# RefOsc10MHz_1V2.net
KiCad netlist of a schematic drawn in EAGLE
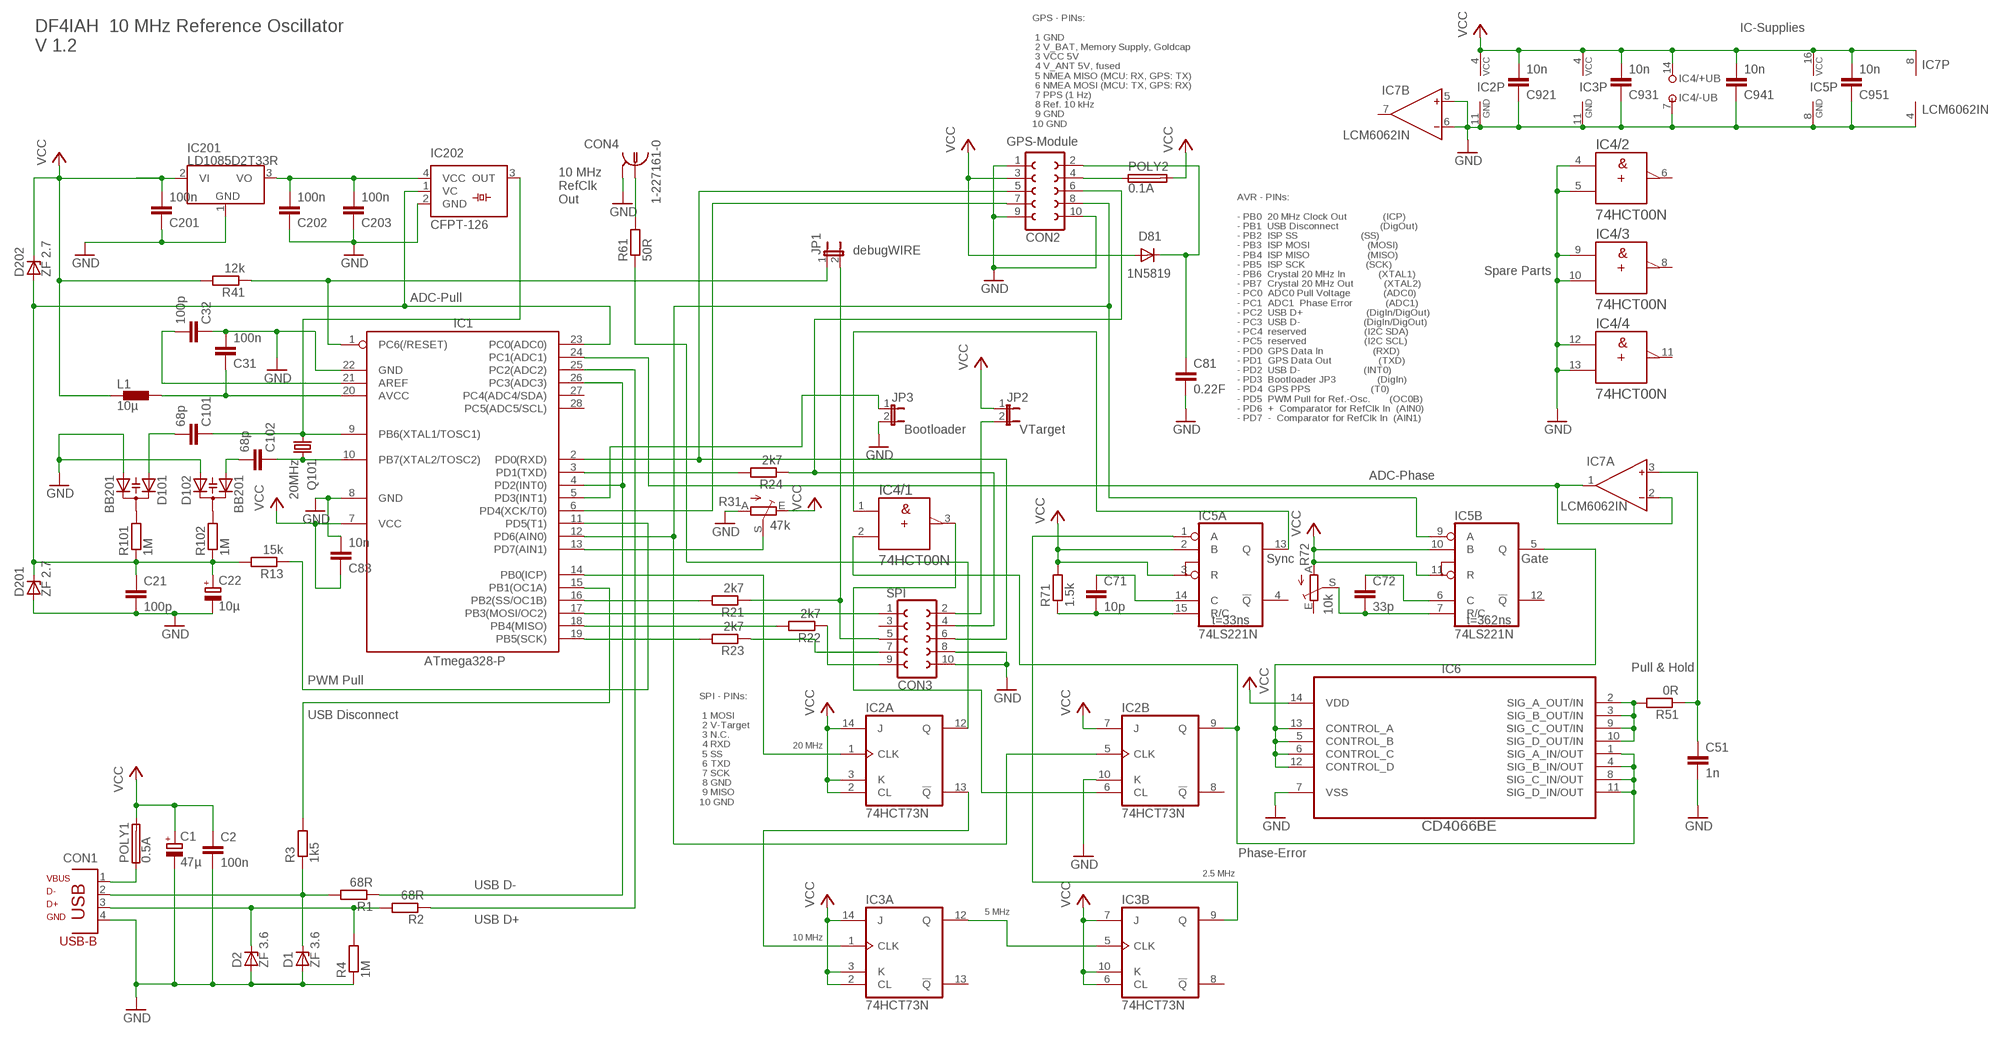
[diagram p0: schematic, sheet 1]

(export (version "E")
  (design (tool "Eeschema 10.0.6"))
  (components
    (comp (ref "C1")
      (value "47µ")
      (footprint "eagle-import:E2-4")
      (libsource (lib "eagle-import") (part "CPOL-EUE2-4"))
    )
    (comp (ref "C2")
      (value "100n")
      (footprint "eagle-import:C5B3")
      (libsource (lib "eagle-import") (part "C5/3"))
    )
    (comp (ref "C21")
      (value "100p")
      (footprint "eagle-import:C5B3")
      (libsource (lib "eagle-import") (part "C5/3"))
    )
    (comp (ref "C22")
      (value "10µ")
      (footprint "eagle-import:E2-4")
      (libsource (lib "eagle-import") (part "CPOL-EUE2-4"))
    )
    (comp (ref "C31")
      (value "100n")
      (footprint "eagle-import:C5B3")
      (libsource (lib "eagle-import") (part "C5/3"))
    )
    (comp (ref "C32")
      (value "100p")
      (footprint "eagle-import:C5B3")
      (libsource (lib "eagle-import") (part "C5/3"))
    )
    (comp (ref "C51")
      (value "1n")
      (footprint "eagle-import:C5B3")
      (libsource (lib "eagle-import") (part "C5/3"))
    )
    (comp (ref "C71")
      (value "10p")
      (footprint "eagle-import:C5B3")
      (libsource (lib "eagle-import") (part "C5/3"))
    )
    (comp (ref "C72")
      (value "33p")
      (footprint "eagle-import:C5B3")
      (libsource (lib "eagle-import") (part "C5/3"))
    )
    (comp (ref "C81")
      (value "0.22F")
      (footprint "eagle-import:C5B7.2")
      (libsource (lib "eagle-import") (part "C5/7.2"))
    )
    (comp (ref "C83")
      (value "10n")
      (footprint "eagle-import:C5B3")
      (libsource (lib "eagle-import") (part "C5/3"))
    )
    (comp (ref "C101")
      (value "68p")
      (footprint "eagle-import:C5B3")
      (libsource (lib "eagle-import") (part "C5/3"))
    )
    (comp (ref "C102")
      (value "68p")
      (footprint "eagle-import:C5B3")
      (libsource (lib "eagle-import") (part "C5/3"))
    )
    (comp (ref "C201")
      (value "100n")
      (footprint "eagle-import:C5B3")
      (libsource (lib "eagle-import") (part "C5/3"))
    )
    (comp (ref "C202")
      (value "100n")
      (footprint "eagle-import:C5B3")
      (libsource (lib "eagle-import") (part "C5/3"))
    )
    (comp (ref "C203")
      (value "100n")
      (footprint "eagle-import:C5B3")
      (libsource (lib "eagle-import") (part "C5/3"))
    )
    (comp (ref "C921")
      (value "10n")
      (footprint "eagle-import:C5B3")
      (libsource (lib "eagle-import") (part "C5/3"))
    )
    (comp (ref "C931")
      (value "10n")
      (footprint "eagle-import:C5B3")
      (libsource (lib "eagle-import") (part "C5/3"))
    )
    (comp (ref "C941")
      (value "10n")
      (footprint "eagle-import:C5B3")
      (libsource (lib "eagle-import") (part "C5/3"))
    )
    (comp (ref "C951")
      (value "10n")
      (footprint "eagle-import:C5B3")
      (libsource (lib "eagle-import") (part "C5/3"))
    )
    (comp (ref "CON1")
      (value "PN61729")
      (footprint "eagle-import:PN61729")
      (libsource (lib "eagle-import") (part "PN61729"))
    )
    (comp (ref "CON2")
      (value "FE05-2")
      (footprint "eagle-import:FE05-2")
      (libsource (lib "eagle-import") (part "FE05-2"))
    )
    (comp (ref "CON3")
      (value "FE05-2")
      (footprint "eagle-import:FE05-2")
      (libsource (lib "eagle-import") (part "FE05-2"))
    )
    (comp (ref "CON4")
      (value "1-227161-0")
      (footprint "eagle-import:AMP_227161")
      (fields (field (name "MF") "TYCO ELECTRONICS") (field (name "MPN") "1-227161"))
      (libsource (lib "eagle-import") (part "?2271611--0"))
    )
    (comp (ref "D1")
      (value "ZF 3.6")
      (footprint "eagle-import:DO41Z10")
      (libsource (lib "eagle-import") (part "1N4728"))
    )
    (comp (ref "D2")
      (value "ZF 3.6")
      (footprint "eagle-import:DO41Z10")
      (libsource (lib "eagle-import") (part "1N4728"))
    )
    (comp (ref "D81")
      (value "1N5819")
      (footprint "eagle-import:DO41-10")
      (libsource (lib "eagle-import") (part "1N4942"))
    )
    (comp (ref "D101")
      (value "BB201")
      (footprint "eagle-import:SOT23")
      (libsource (lib "eagle-import") (part "BBY51"))
    )
    (comp (ref "D102")
      (value "BB201")
      (footprint "eagle-import:SOT23")
      (libsource (lib "eagle-import") (part "BBY51"))
    )
    (comp (ref "D201")
      (value "ZF 2.7")
      (footprint "eagle-import:DO41Z10")
      (libsource (lib "eagle-import") (part "1N4728"))
    )
    (comp (ref "D202")
      (value "ZF 2.7")
      (footprint "eagle-import:DO41Z10")
      (libsource (lib "eagle-import") (part "1N4728"))
    )
    (comp (ref "IC1")
      (value "ATmega328-P")
      (footprint "eagle-import:DIL28-3")
      (libsource (lib "eagle-import") (part "MEGA8-P"))
    )
    (comp (ref "IC2")
      (value "74HCT73N")
      (footprint "eagle-import:DIL14")
      (libsource (lib "eagle-import") (part "7473NLS"))
    )
    (comp (ref "IC3")
      (value "74HCT73N")
      (footprint "eagle-import:DIL14")
      (libsource (lib "eagle-import") (part "7473NLS"))
    )
    (comp (ref "IC4")
      (value "74HCT00N")
      (footprint "eagle-import:DIL14")
      (libsource (lib "eagle-import") (part "7400NHCT"))
    )
    (comp (ref "IC5")
      (value "74LS221N")
      (footprint "eagle-import:DIL16")
      (libsource (lib "eagle-import") (part "74221NLS"))
    )
    (comp (ref "IC6")
      (value "CD4066BE")
      (footprint "eagle-import:DIP254P762X508-14")
      (libsource (lib "eagle-import") (part "CD4066BE"))
    )
    (comp (ref "IC7")
      (value "LCM6062IN")
      (footprint "eagle-import:DIL08")
      (libsource (lib "eagle-import") (part "AD822IN"))
    )
    (comp (ref "IC201")
      (value "LD10853.3")
      (footprint "eagle-import:TO220V")
      (libsource (lib "eagle-import") (part "LD10853.3"))
    )
    (comp (ref "IC202")
      (value "CFPT-126")
      (footprint "eagle-import:SM77H")
      (libsource (lib "eagle-import") (part "CFPT-126"))
    )
    (comp (ref "JP1")
      (value "JP1E")
      (footprint "eagle-import:JP1")
      (libsource (lib "eagle-import") (part "JP1E"))
    )
    (comp (ref "JP2")
      (value "JP1E")
      (footprint "eagle-import:JP1")
      (libsource (lib "eagle-import") (part "JP1E"))
    )
    (comp (ref "JP3")
      (value "JP1E")
      (footprint "eagle-import:JP1")
      (libsource (lib "eagle-import") (part "JP1E"))
    )
    (comp (ref "L1")
      (value "10µ")
      (footprint "eagle-import:BL01RN1A")
      (libsource (lib "eagle-import") (part "BL01RN1A"))
    )
    (comp (ref "POLY1")
      (value "0.5A")
      (footprint "eagle-import:TE5")
      (libsource (lib "eagle-import") (part "FUSETE5"))
    )
    (comp (ref "POLY2")
      (value "0.1A")
      (footprint "eagle-import:TE5")
      (libsource (lib "eagle-import") (part "FUSETE5"))
    )
    (comp (ref "Q101")
      (value "20MHz")
      (footprint "eagle-import:HC49U70")
      (libsource (lib "eagle-import") (part "CRYSTALHC49U70"))
    )
    (comp (ref "R1")
      (value "68R")
      (footprint "eagle-import:0204_7")
      (libsource (lib "eagle-import") (part "R-EU_0204/7"))
    )
    (comp (ref "R2")
      (value "68R")
      (footprint "eagle-import:0204_7")
      (libsource (lib "eagle-import") (part "R-EU_0204/7"))
    )
    (comp (ref "R3")
      (value "1k5")
      (footprint "eagle-import:0204_7")
      (libsource (lib "eagle-import") (part "R-EU_0204/7"))
    )
    (comp (ref "R4")
      (value "1M")
      (footprint "eagle-import:0204_7")
      (libsource (lib "eagle-import") (part "R-EU_0204/7"))
    )
    (comp (ref "R13")
      (value "15k")
      (footprint "eagle-import:0204_7")
      (libsource (lib "eagle-import") (part "R-EU_0204/7"))
    )
    (comp (ref "R21")
      (value "2k7")
      (footprint "eagle-import:0204_7")
      (libsource (lib "eagle-import") (part "R-EU_0204/7"))
    )
    (comp (ref "R22")
      (value "2k7")
      (footprint "eagle-import:0204_7")
      (libsource (lib "eagle-import") (part "R-EU_0204/7"))
    )
    (comp (ref "R23")
      (value "2k7")
      (footprint "eagle-import:0204_7")
      (libsource (lib "eagle-import") (part "R-EU_0204/7"))
    )
    (comp (ref "R24")
      (value "2k7")
      (footprint "eagle-import:0204_7")
      (libsource (lib "eagle-import") (part "R-EU_0204/7"))
    )
    (comp (ref "R31")
      (value "47k")
      (footprint "eagle-import:S64YW")
      (libsource (lib "eagle-import") (part "TRIM_1234-S64YW"))
    )
    (comp (ref "R41")
      (value "12k")
      (footprint "eagle-import:0204_7")
      (libsource (lib "eagle-import") (part "R-EU_0204/7"))
    )
    (comp (ref "R51")
      (value "0R")
      (footprint "eagle-import:0204_7")
      (libsource (lib "eagle-import") (part "R-EU_0204/7"))
    )
    (comp (ref "R61")
      (value "50R")
      (footprint "eagle-import:0204_7")
      (libsource (lib "eagle-import") (part "R-EU_0204/7"))
    )
    (comp (ref "R71")
      (value "1.5k")
      (footprint "eagle-import:0204_7")
      (libsource (lib "eagle-import") (part "R-EU_0204/7"))
    )
    (comp (ref "R72")
      (value "10k")
      (footprint "eagle-import:S64YW")
      (libsource (lib "eagle-import") (part "TRIM_1234-S64YW"))
    )
    (comp (ref "R101")
      (value "1M")
      (footprint "eagle-import:0204_7")
      (libsource (lib "eagle-import") (part "R-EU_0204/7"))
    )
    (comp (ref "R102")
      (value "1M")
      (footprint "eagle-import:0204_7")
      (libsource (lib "eagle-import") (part "R-EU_0204/7"))
    )
  )
  (nets
    (net (code "1") (name "GND") (class "Default")
      (node (ref "C1") (pin "-") (pinfunction "-_-") (pintype "passive"))
      (node (ref "C2") (pin "2") (pinfunction "2_2") (pintype "passive"))
      (node (ref "C201") (pin "1") (pinfunction "1_1") (pintype "passive"))
      (node (ref "C202") (pin "1") (pinfunction "1_1") (pintype "passive"))
      (node (ref "C203") (pin "1") (pinfunction "1_1") (pintype "passive"))
      (node (ref "C21") (pin "2") (pinfunction "2_2") (pintype "passive"))
      (node (ref "C22") (pin "-") (pinfunction "-_-") (pintype "passive"))
      (node (ref "C31") (pin "2") (pinfunction "2_2") (pintype "passive"))
      (node (ref "C32") (pin "1") (pinfunction "1_1") (pintype "passive"))
      (node (ref "C51") (pin "2") (pinfunction "2_2") (pintype "passive"))
      (node (ref "C81") (pin "2") (pinfunction "2_2") (pintype "passive"))
      (node (ref "C83") (pin "2") (pinfunction "2_2") (pintype "passive"))
      (node (ref "C921") (pin "1") (pinfunction "1_1") (pintype "passive"))
      (node (ref "C931") (pin "1") (pinfunction "1_1") (pintype "passive"))
      (node (ref "C941") (pin "1") (pinfunction "1_1") (pintype "passive"))
      (node (ref "C951") (pin "1") (pinfunction "1_1") (pintype "passive"))
      (node (ref "CON1") (pin "4") (pinfunction "4_4") (pintype "passive"))
      (node (ref "CON2") (pin "1") (pinfunction "1_1") (pintype "passive"))
      (node (ref "CON2") (pin "10") (pinfunction "10_10") (pintype "passive"))
      (node (ref "CON2") (pin "9") (pinfunction "9_9") (pintype "passive"))
      (node (ref "CON3") (pin "10") (pinfunction "10_10") (pintype "passive"))
      (node (ref "CON3") (pin "8") (pinfunction "8_8") (pintype "passive"))
      (node (ref "CON4") (pin "2") (pinfunction "2_2") (pintype "passive"))
      (node (ref "D1") (pin "A") (pinfunction "A_A") (pintype "passive"))
      (node (ref "D101") (pin "2") (pinfunction "A2_2") (pintype "passive"))
      (node (ref "D102") (pin "1") (pinfunction "A1_1") (pintype "passive"))
      (node (ref "D2") (pin "A") (pinfunction "A_A") (pintype "passive"))
      (node (ref "D201") (pin "A") (pinfunction "A_A") (pintype "passive"))
      (node (ref "IC1") (pin "22") (pinfunction "GND_22") (pintype "power_in"))
      (node (ref "IC1") (pin "8") (pinfunction "GND_8") (pintype "power_in"))
      (node (ref "IC2") (pin "10") (pinfunction "K_10") (pintype "input"))
      (node (ref "IC2") (pin "11") (pinfunction "GND_11") (pintype "power_in"))
      (node (ref "IC201") (pin "1") (pinfunction "GND_1") (pintype "passive"))
      (node (ref "IC202") (pin "2") (pinfunction "GND_2") (pintype "power_in"))
      (node (ref "IC3") (pin "11") (pinfunction "GND_11") (pintype "power_in"))
      (node (ref "IC4") (pin "10") (pinfunction "B_10") (pintype "input"))
      (node (ref "IC4") (pin "12") (pinfunction "A_12") (pintype "input"))
      (node (ref "IC4") (pin "13") (pinfunction "B_13") (pintype "input"))
      (node (ref "IC4") (pin "4") (pinfunction "A_4") (pintype "input"))
      (node (ref "IC4") (pin "5") (pinfunction "B_5") (pintype "input"))
      (node (ref "IC4") (pin "7") (pinfunction "-UB_7") (pintype "power_in"))
      (node (ref "IC4") (pin "9") (pinfunction "A_9") (pintype "input"))
      (node (ref "IC5") (pin "8") (pinfunction "GND_8") (pintype "power_in"))
      (node (ref "IC6") (pin "7") (pinfunction "VSS_7") (pintype "passive"))
      (node (ref "IC7") (pin "4") (pinfunction "V-_4") (pintype "power_in"))
      (node (ref "IC7") (pin "5") (pinfunction "IN+_5") (pintype "input"))
      (node (ref "IC7") (pin "6") (pinfunction "IN-_6") (pintype "input"))
      (node (ref "JP3") (pin "2") (pinfunction "2_2") (pintype "passive"))
      (node (ref "R31") (pin "A") (pinfunction "A_A") (pintype "passive"))
      (node (ref "R4") (pin "1") (pinfunction "1_1") (pintype "passive"))
    )
    (net (code "2") (name "Net-(C81-Pad1)") (class "Default")
      (node (ref "C81") (pin "1") (pinfunction "1_1") (pintype "passive"))
      (node (ref "CON2") (pin "2") (pinfunction "2_2") (pintype "passive"))
      (node (ref "D81") (pin "C") (pinfunction "C_C") (pintype "passive"))
    )
    (net (code "3") (name "Net-(CON1-Pad1)") (class "Default")
      (node (ref "CON1") (pin "1") (pinfunction "1_1") (pintype "passive"))
      (node (ref "POLY1") (pin "1") (pinfunction "1_1") (pintype "passive"))
    )
    (net (code "4") (name "Net-(CON1-Pad2)") (class "Default")
      (node (ref "CON1") (pin "2") (pinfunction "2_2") (pintype "passive"))
      (node (ref "D1") (pin "C") (pinfunction "C_C") (pintype "passive"))
      (node (ref "R1") (pin "2") (pinfunction "2_2") (pintype "passive"))
      (node (ref "R3") (pin "1") (pinfunction "1_1") (pintype "passive"))
    )
    (net (code "5") (name "Net-(CON1-Pad3)") (class "Default")
      (node (ref "CON1") (pin "3") (pinfunction "3_3") (pintype "passive"))
      (node (ref "D2") (pin "C") (pinfunction "C_C") (pintype "passive"))
      (node (ref "R2") (pin "2") (pinfunction "2_2") (pintype "passive"))
      (node (ref "R4") (pin "2") (pinfunction "2_2") (pintype "passive"))
    )
    (net (code "6") (name "Net-(CON2-Pad4)") (class "Default")
      (node (ref "CON2") (pin "4") (pinfunction "4_4") (pintype "passive"))
      (node (ref "POLY2") (pin "1") (pinfunction "1_1") (pintype "passive"))
    )
    (net (code "7") (name "Net-(CON2-Pad6)") (class "Default")
      (node (ref "CON2") (pin "6") (pinfunction "6_6") (pintype "passive"))
      (node (ref "CON3") (pin "4") (pinfunction "4_4") (pintype "passive"))
      (node (ref "R24") (pin "1") (pinfunction "1_1") (pintype "passive"))
    )
    (net (code "8") (name "Net-(CON3-Pad2)") (class "Default")
      (node (ref "CON3") (pin "2") (pinfunction "2_2") (pintype "passive"))
      (node (ref "JP2") (pin "2") (pinfunction "2_2") (pintype "passive"))
    )
    (net (code "9") (name "Net-(CON3-Pad5)") (class "Default")
      (node (ref "CON3") (pin "5") (pinfunction "5_5") (pintype "passive"))
      (node (ref "JP1") (pin "2") (pinfunction "2_2") (pintype "passive"))
      (node (ref "R21") (pin "1") (pinfunction "1_1") (pintype "passive"))
    )
    (net (code "10") (name "Net-(CON3-Pad7)") (class "Default")
      (node (ref "CON3") (pin "7") (pinfunction "7_7") (pintype "passive"))
      (node (ref "R23") (pin "1") (pinfunction "1_1") (pintype "passive"))
    )
    (net (code "11") (name "Net-(CON3-Pad9)") (class "Default")
      (node (ref "CON3") (pin "9") (pinfunction "9_9") (pintype "passive"))
      (node (ref "R22") (pin "1") (pinfunction "1_1") (pintype "passive"))
    )
    (net (code "12") (name "Net-(CON4-Pad1)") (class "Default")
      (node (ref "CON4") (pin "1") (pinfunction "1_1") (pintype "passive"))
      (node (ref "R61") (pin "2") (pinfunction "2_2") (pintype "passive"))
    )
    (net (code "13") (name "Net-(D101-A1)") (class "Default")
      (node (ref "C101") (pin "2") (pinfunction "2_2") (pintype "passive"))
      (node (ref "D101") (pin "1") (pinfunction "A1_1") (pintype "passive"))
    )
    (net (code "14") (name "Net-(D101-C)") (class "Default")
      (node (ref "D101") (pin "3") (pinfunction "C_3") (pintype "passive"))
      (node (ref "R101") (pin "2") (pinfunction "2_2") (pintype "passive"))
    )
    (net (code "15") (name "Net-(D102-A2)") (class "Default")
      (node (ref "C102") (pin "2") (pinfunction "2_2") (pintype "passive"))
      (node (ref "D102") (pin "2") (pinfunction "A2_2") (pintype "passive"))
    )
    (net (code "16") (name "Net-(D102-C)") (class "Default")
      (node (ref "D102") (pin "3") (pinfunction "C_3") (pintype "passive"))
      (node (ref "R102") (pin "2") (pinfunction "2_2") (pintype "passive"))
    )
    (net (code "17") (name "Net-(IC1-AREF)") (class "Default")
      (node (ref "C32") (pin "2") (pinfunction "2_2") (pintype "passive"))
      (node (ref "IC1") (pin "21") (pinfunction "AREF_21") (pintype "passive"))
    )
    (net (code "18") (name "Net-(IC1-AVCC)") (class "Default")
      (node (ref "C31") (pin "1") (pinfunction "1_1") (pintype "passive"))
      (node (ref "IC1") (pin "20") (pinfunction "AVCC_20") (pintype "power_in"))
      (node (ref "L1") (pin "2") (pinfunction "2_2") (pintype "passive"))
    )
    (net (code "19") (name "Net-(IC1-PB0(ICP))") (class "Default")
      (node (ref "IC1") (pin "14") (pinfunction "PB0(ICP)_14") (pintype "bidirectional"))
      (node (ref "IC2") (pin "1") (pinfunction "CLK_1") (pintype "input"))
    )
    (net (code "20") (name "Net-(IC1-PB1(OC1A))") (class "Default")
      (node (ref "IC1") (pin "15") (pinfunction "PB1(OC1A)_15") (pintype "bidirectional"))
      (node (ref "R3") (pin "2") (pinfunction "2_2") (pintype "passive"))
    )
    (net (code "21") (name "Net-(IC1-PB2(SS{slash}OC1B))") (class "Default")
      (node (ref "IC1") (pin "16") (pinfunction "PB2(SS/OC1B)_16") (pintype "bidirectional"))
      (node (ref "R21") (pin "2") (pinfunction "2_2") (pintype "passive"))
    )
    (net (code "22") (name "Net-(IC1-PB3(MOSI{slash}OC2))") (class "Default")
      (node (ref "CON3") (pin "1") (pinfunction "1_1") (pintype "passive"))
      (node (ref "IC1") (pin "17") (pinfunction "PB3(MOSI/OC2)_17") (pintype "bidirectional"))
    )
    (net (code "23") (name "Net-(IC1-PB4(MISO))") (class "Default")
      (node (ref "IC1") (pin "18") (pinfunction "PB4(MISO)_18") (pintype "bidirectional"))
      (node (ref "R22") (pin "2") (pinfunction "2_2") (pintype "passive"))
    )
    (net (code "24") (name "Net-(IC1-PB5(SCK))") (class "Default")
      (node (ref "IC1") (pin "19") (pinfunction "PB5(SCK)_19") (pintype "bidirectional"))
      (node (ref "R23") (pin "2") (pinfunction "2_2") (pintype "passive"))
    )
    (net (code "25") (name "Net-(IC1-PB6(XTAL1{slash}TOSC1))") (class "Default")
      (node (ref "C101") (pin "1") (pinfunction "1_1") (pintype "passive"))
      (node (ref "IC1") (pin "9") (pinfunction "PB6(XTAL1/TOSC1)_9") (pintype "bidirectional"))
      (node (ref "IC202") (pin "3") (pinfunction "OUT_3") (pintype "output"))
      (node (ref "Q101") (pin "1") (pinfunction "1_1") (pintype "passive"))
    )
    (net (code "26") (name "Net-(IC1-PB7(XTAL2{slash}TOSC2))") (class "Default")
      (node (ref "C102") (pin "1") (pinfunction "1_1") (pintype "passive"))
      (node (ref "IC1") (pin "10") (pinfunction "PB7(XTAL2/TOSC2)_10") (pintype "bidirectional"))
      (node (ref "Q101") (pin "2") (pinfunction "2_2") (pintype "passive"))
    )
    (net (code "27") (name "Net-(IC1-PC0(ADC0))") (class "Default")
      (node (ref "C21") (pin "1") (pinfunction "1_1") (pintype "passive"))
      (node (ref "C22") (pin "+") (pinfunction "+_+") (pintype "passive"))
      (node (ref "D201") (pin "C") (pinfunction "C_C") (pintype "passive"))
      (node (ref "D202") (pin "A") (pinfunction "A_A") (pintype "passive"))
      (node (ref "IC1") (pin "23") (pinfunction "PC0(ADC0)_23") (pintype "bidirectional"))
      (node (ref "IC202") (pin "1") (pinfunction "VC_1") (pintype "input"))
      (node (ref "R101") (pin "1") (pinfunction "1_1") (pintype "passive"))
      (node (ref "R102") (pin "1") (pinfunction "1_1") (pintype "passive"))
      (node (ref "R13") (pin "2") (pinfunction "2_2") (pintype "passive"))
    )
    (net (code "28") (name "Net-(IC1-PC1(ADC1))") (class "Default")
      (node (ref "IC1") (pin "24") (pinfunction "PC1(ADC1)_24") (pintype "bidirectional"))
      (node (ref "IC7") (pin "1") (pinfunction "OUT_1") (pintype "output"))
      (node (ref "IC7") (pin "2") (pinfunction "IN-_2") (pintype "input"))
    )
    (net (code "29") (name "Net-(IC1-PC2(ADC2))") (class "Default")
      (node (ref "IC1") (pin "25") (pinfunction "PC2(ADC2)_25") (pintype "bidirectional"))
      (node (ref "R2") (pin "1") (pinfunction "1_1") (pintype "passive"))
    )
    (net (code "30") (name "Net-(IC1-PC3(ADC3))") (class "Default")
      (node (ref "IC1") (pin "26") (pinfunction "PC3(ADC3)_26") (pintype "bidirectional"))
      (node (ref "IC1") (pin "4") (pinfunction "PD2(INT0)_4") (pintype "bidirectional"))
      (node (ref "R1") (pin "1") (pinfunction "1_1") (pintype "passive"))
    )
    (net (code "31") (name "Net-(IC1-PC6({slash}RESET))") (class "Default")
      (node (ref "IC1") (pin "1") (pinfunction "PC6(/RESET)_1") (pintype "bidirectional"))
      (node (ref "JP1") (pin "1") (pinfunction "1_1") (pintype "passive"))
      (node (ref "R41") (pin "1") (pinfunction "1_1") (pintype "passive"))
    )
    (net (code "32") (name "Net-(IC1-PD0(RXD))") (class "Default")
      (node (ref "CON2") (pin "5") (pinfunction "5_5") (pintype "passive"))
      (node (ref "CON3") (pin "6") (pinfunction "6_6") (pintype "passive"))
      (node (ref "IC1") (pin "2") (pinfunction "PD0(RXD)_2") (pintype "bidirectional"))
    )
    (net (code "33") (name "Net-(IC1-PD1(TXD))") (class "Default")
      (node (ref "IC1") (pin "3") (pinfunction "PD1(TXD)_3") (pintype "bidirectional"))
      (node (ref "R24") (pin "2") (pinfunction "2_2") (pintype "passive"))
    )
    (net (code "34") (name "Net-(IC1-PD3(INT1))") (class "Default")
      (node (ref "IC1") (pin "5") (pinfunction "PD3(INT1)_5") (pintype "bidirectional"))
      (node (ref "JP3") (pin "1") (pinfunction "1_1") (pintype "passive"))
    )
    (net (code "35") (name "Net-(IC1-PD4(XCK{slash}T0))") (class "Default")
      (node (ref "CON2") (pin "7") (pinfunction "7_7") (pintype "passive"))
      (node (ref "IC1") (pin "6") (pinfunction "PD4(XCK/T0)_6") (pintype "bidirectional"))
    )
    (net (code "36") (name "Net-(IC1-PD5(T1))") (class "Default")
      (node (ref "IC1") (pin "11") (pinfunction "PD5(T1)_11") (pintype "bidirectional"))
      (node (ref "R13") (pin "1") (pinfunction "1_1") (pintype "passive"))
    )
    (net (code "37") (name "Net-(IC1-PD6(AIN0))") (class "Default")
      (node (ref "CON2") (pin "8") (pinfunction "8_8") (pintype "passive"))
      (node (ref "IC1") (pin "12") (pinfunction "PD6(AIN0)_12") (pintype "bidirectional"))
      (node (ref "IC2") (pin "5") (pinfunction "CLK_5") (pintype "input"))
      (node (ref "IC5") (pin "9") (pinfunction "A_9") (pintype "input"))
    )
    (net (code "38") (name "Net-(IC1-PD7(AIN1))") (class "Default")
      (node (ref "IC1") (pin "13") (pinfunction "PD7(AIN1)_13") (pintype "bidirectional"))
      (node (ref "R31") (pin "S") (pinfunction "S_S") (pintype "passive"))
    )
    (net (code "39") (name "Net-(IC2A-Q)") (class "Default")
      (node (ref "IC2") (pin "12") (pinfunction "Q_12") (pintype "output"))
      (node (ref "R61") (pin "1") (pinfunction "1_1") (pintype "passive"))
    )
    (net (code "40") (name "Net-(IC2A-~{Q})") (class "Default")
      (node (ref "IC2") (pin "13") (pinfunction "~{Q}_13") (pintype "output"))
      (node (ref "IC3") (pin "1") (pinfunction "CLK_1") (pintype "input"))
    )
    (net (code "41") (name "Net-(IC2B-CL)") (class "Default")
      (node (ref "IC2") (pin "6") (pinfunction "CL_6") (pintype "input"))
      (node (ref "IC4") (pin "3") (pinfunction "Y_3") (pintype "output"))
    )
    (net (code "42") (name "Net-(IC2B-Q)") (class "Default")
      (node (ref "IC2") (pin "9") (pinfunction "Q_9") (pintype "output"))
      (node (ref "IC4") (pin "2") (pinfunction "B_2") (pintype "input"))
      (node (ref "IC6") (pin "1") (pinfunction "SIG_A_IN/OUT_1") (pintype "bidirectional"))
      (node (ref "IC6") (pin "11") (pinfunction "SIG_D_IN/OUT_11") (pintype "bidirectional"))
      (node (ref "IC6") (pin "4") (pinfunction "SIG_B_IN/OUT_4") (pintype "bidirectional"))
      (node (ref "IC6") (pin "8") (pinfunction "SIG_C_IN/OUT_8") (pintype "bidirectional"))
    )
    (net (code "43") (name "Net-(IC3A-Q)") (class "Default")
      (node (ref "IC3") (pin "12") (pinfunction "Q_12") (pintype "output"))
      (node (ref "IC3") (pin "5") (pinfunction "CLK_5") (pintype "input"))
    )
    (net (code "44") (name "Net-(IC3B-Q)") (class "Default")
      (node (ref "IC3") (pin "9") (pinfunction "Q_9") (pintype "output"))
      (node (ref "IC5") (pin "1") (pinfunction "A_1") (pintype "input"))
    )
    (net (code "45") (name "Net-(IC4C-A)") (class "Default")
      (node (ref "IC4") (pin "1") (pinfunction "A_1") (pintype "input"))
      (node (ref "IC5") (pin "13") (pinfunction "Q_13") (pintype "output"))
    )
    (net (code "46") (name "Net-(IC5A-C)") (class "Default")
      (node (ref "C71") (pin "1") (pinfunction "1_1") (pintype "passive"))
      (node (ref "IC5") (pin "14") (pinfunction "C_14") (pintype "input"))
    )
    (net (code "47") (name "Net-(IC5A-R{slash}C)") (class "Default")
      (node (ref "C71") (pin "2") (pinfunction "2_2") (pintype "passive"))
      (node (ref "IC5") (pin "15") (pinfunction "R/C_15") (pintype "input"))
      (node (ref "R71") (pin "1") (pinfunction "1_1") (pintype "passive"))
    )
    (net (code "48") (name "Net-(IC5B-C)") (class "Default")
      (node (ref "C72") (pin "1") (pinfunction "1_1") (pintype "passive"))
      (node (ref "IC5") (pin "6") (pinfunction "C_6") (pintype "input"))
    )
    (net (code "49") (name "Net-(IC5B-Q)") (class "Default")
      (node (ref "IC5") (pin "5") (pinfunction "Q_5") (pintype "output"))
      (node (ref "IC6") (pin "12") (pinfunction "CONTROL_D_12") (pintype "input"))
      (node (ref "IC6") (pin "13") (pinfunction "CONTROL_A_13") (pintype "input"))
      (node (ref "IC6") (pin "5") (pinfunction "CONTROL_B_5") (pintype "input"))
      (node (ref "IC6") (pin "6") (pinfunction "CONTROL_C_6") (pintype "input"))
    )
    (net (code "50") (name "Net-(IC5B-R{slash}C)") (class "Default")
      (node (ref "C72") (pin "2") (pinfunction "2_2") (pintype "passive"))
      (node (ref "IC5") (pin "7") (pinfunction "R/C_7") (pintype "input"))
      (node (ref "R72") (pin "S") (pinfunction "S_S") (pintype "passive"))
    )
    (net (code "51") (name "Net-(IC6-SIG_A_OUT{slash}IN)") (class "Default")
      (node (ref "IC6") (pin "10") (pinfunction "SIG_D_OUT/IN_10") (pintype "bidirectional"))
      (node (ref "IC6") (pin "2") (pinfunction "SIG_A_OUT/IN_2") (pintype "bidirectional"))
      (node (ref "IC6") (pin "3") (pinfunction "SIG_B_OUT/IN_3") (pintype "bidirectional"))
      (node (ref "IC6") (pin "9") (pinfunction "SIG_C_OUT/IN_9") (pintype "bidirectional"))
      (node (ref "R51") (pin "2") (pinfunction "2_2") (pintype "passive"))
    )
    (net (code "52") (name "Net-(IC7A-IN+)") (class "Default")
      (node (ref "C51") (pin "1") (pinfunction "1_1") (pintype "passive"))
      (node (ref "IC7") (pin "3") (pinfunction "IN+_3") (pintype "input"))
      (node (ref "R51") (pin "1") (pinfunction "1_1") (pintype "passive"))
    )
    (net (code "53") (name "Net-(IC201-VO)") (class "Default")
      (node (ref "C202") (pin "2") (pinfunction "2_2") (pintype "passive"))
      (node (ref "C203") (pin "2") (pinfunction "2_2") (pintype "passive"))
      (node (ref "IC201") (pin "3") (pinfunction "VO_3") (pintype "passive"))
      (node (ref "IC202") (pin "4") (pinfunction "VCC_4") (pintype "power_in"))
    )
    (net (code "54") (name "VCC") (class "Default")
      (node (ref "C1") (pin "+") (pinfunction "+_+") (pintype "passive"))
      (node (ref "C2") (pin "1") (pinfunction "1_1") (pintype "passive"))
      (node (ref "C201") (pin "2") (pinfunction "2_2") (pintype "passive"))
      (node (ref "C83") (pin "1") (pinfunction "1_1") (pintype "passive"))
      (node (ref "C921") (pin "2") (pinfunction "2_2") (pintype "passive"))
      (node (ref "C931") (pin "2") (pinfunction "2_2") (pintype "passive"))
      (node (ref "C941") (pin "2") (pinfunction "2_2") (pintype "passive"))
      (node (ref "C951") (pin "2") (pinfunction "2_2") (pintype "passive"))
      (node (ref "CON2") (pin "3") (pinfunction "3_3") (pintype "passive"))
      (node (ref "D202") (pin "C") (pinfunction "C_C") (pintype "passive"))
      (node (ref "D81") (pin "A") (pinfunction "A_A") (pintype "passive"))
      (node (ref "IC1") (pin "7") (pinfunction "VCC_7") (pintype "power_in"))
      (node (ref "IC2") (pin "14") (pinfunction "J_14") (pintype "input"))
      (node (ref "IC2") (pin "2") (pinfunction "CL_2") (pintype "input"))
      (node (ref "IC2") (pin "3") (pinfunction "K_3") (pintype "input"))
      (node (ref "IC2") (pin "4") (pinfunction "VCC_4") (pintype "power_in"))
      (node (ref "IC2") (pin "7") (pinfunction "J_7") (pintype "input"))
      (node (ref "IC201") (pin "2") (pinfunction "VI_2") (pintype "input"))
      (node (ref "IC3") (pin "10") (pinfunction "K_10") (pintype "input"))
      (node (ref "IC3") (pin "14") (pinfunction "J_14") (pintype "input"))
      (node (ref "IC3") (pin "2") (pinfunction "CL_2") (pintype "input"))
      (node (ref "IC3") (pin "3") (pinfunction "K_3") (pintype "input"))
      (node (ref "IC3") (pin "4") (pinfunction "VCC_4") (pintype "power_in"))
      (node (ref "IC3") (pin "6") (pinfunction "CL_6") (pintype "input"))
      (node (ref "IC3") (pin "7") (pinfunction "J_7") (pintype "input"))
      (node (ref "IC4") (pin "14") (pinfunction "+UB_14") (pintype "power_in"))
      (node (ref "IC5") (pin "10") (pinfunction "B_10") (pintype "input"))
      (node (ref "IC5") (pin "11") (pinfunction "R_11") (pintype "input"))
      (node (ref "IC5") (pin "16") (pinfunction "VCC_16") (pintype "power_in"))
      (node (ref "IC5") (pin "2") (pinfunction "B_2") (pintype "input"))
      (node (ref "IC5") (pin "3") (pinfunction "R_3") (pintype "input"))
      (node (ref "IC6") (pin "14") (pinfunction "VDD_14") (pintype "power_in"))
      (node (ref "IC7") (pin "8") (pinfunction "V+_8") (pintype "power_in"))
      (node (ref "JP2") (pin "1") (pinfunction "1_1") (pintype "passive"))
      (node (ref "L1") (pin "1") (pinfunction "1_1") (pintype "passive"))
      (node (ref "POLY1") (pin "2") (pinfunction "2_2") (pintype "passive"))
      (node (ref "POLY2") (pin "2") (pinfunction "2_2") (pintype "passive"))
      (node (ref "R31") (pin "E") (pinfunction "E_E") (pintype "passive"))
      (node (ref "R41") (pin "2") (pinfunction "2_2") (pintype "passive"))
      (node (ref "R71") (pin "2") (pinfunction "2_2") (pintype "passive"))
      (node (ref "R72") (pin "A") (pinfunction "A_A") (pintype "passive"))
    )
    (net (code "55") (name "unconnected-(CON3-Pad3)") (class "Default")
      (node (ref "CON3") (pin "3") (pinfunction "3_3") (pintype "passive"))
    )
    (net (code "56") (name "unconnected-(IC1-PC4(ADC4{slash}SDA)-Pad27)") (class "Default")
      (node (ref "IC1") (pin "27") (pinfunction "PC4(ADC4/SDA)_27") (pintype "bidirectional"))
    )
    (net (code "57") (name "unconnected-(IC1-PC5(ADC5{slash}SCL)-Pad28)") (class "Default")
      (node (ref "IC1") (pin "28") (pinfunction "PC5(ADC5/SCL)_28") (pintype "bidirectional"))
    )
    (net (code "58") (name "unconnected-(IC2B-~{Q}-Pad8)") (class "Default")
      (node (ref "IC2") (pin "8") (pinfunction "~{Q}_8") (pintype "output"))
    )
    (net (code "59") (name "unconnected-(IC3A-~{Q}-Pad13)") (class "Default")
      (node (ref "IC3") (pin "13") (pinfunction "~{Q}_13") (pintype "output"))
    )
    (net (code "60") (name "unconnected-(IC3B-~{Q}-Pad8)") (class "Default")
      (node (ref "IC3") (pin "8") (pinfunction "~{Q}_8") (pintype "output"))
    )
    (net (code "61") (name "unconnected-(IC4D-Y-Pad6)") (class "Default")
      (node (ref "IC4") (pin "6") (pinfunction "Y_6") (pintype "output"))
    )
    (net (code "62") (name "unconnected-(IC4E-Y-Pad8)") (class "Default")
      (node (ref "IC4") (pin "8") (pinfunction "Y_8") (pintype "output"))
    )
    (net (code "63") (name "unconnected-(IC4F-Y-Pad11)") (class "Default")
      (node (ref "IC4") (pin "11") (pinfunction "Y_11") (pintype "output"))
    )
    (net (code "64") (name "unconnected-(IC5A-~{Q}-Pad4)") (class "Default")
      (node (ref "IC5") (pin "4") (pinfunction "~{Q}_4") (pintype "output"))
    )
    (net (code "65") (name "unconnected-(IC5B-~{Q}-Pad12)") (class "Default")
      (node (ref "IC5") (pin "12") (pinfunction "~{Q}_12") (pintype "output"))
    )
    (net (code "66") (name "unconnected-(IC7B-OUT-Pad7)") (class "Default")
      (node (ref "IC7") (pin "7") (pinfunction "OUT_7") (pintype "output"))
    )
    (net (code "67") (name "unconnected-(R31-S-PadS@1)") (class "Default")
      (node (ref "R31") (pin "S@1") (pinfunction "S_S@1") (pintype "passive"))
    )
    (net (code "68") (name "unconnected-(R72-PadE)") (class "Default")
      (node (ref "R72") (pin "E") (pinfunction "E_E") (pintype "passive"))
    )
    (net (code "69") (name "unconnected-(R72-S-PadS@1)") (class "Default")
      (node (ref "R72") (pin "S@1") (pinfunction "S_S@1") (pintype "passive"))
    )
  )
)
